# Chassis_Board.net
KiCad netlist of a schematic drawn in EAGLE
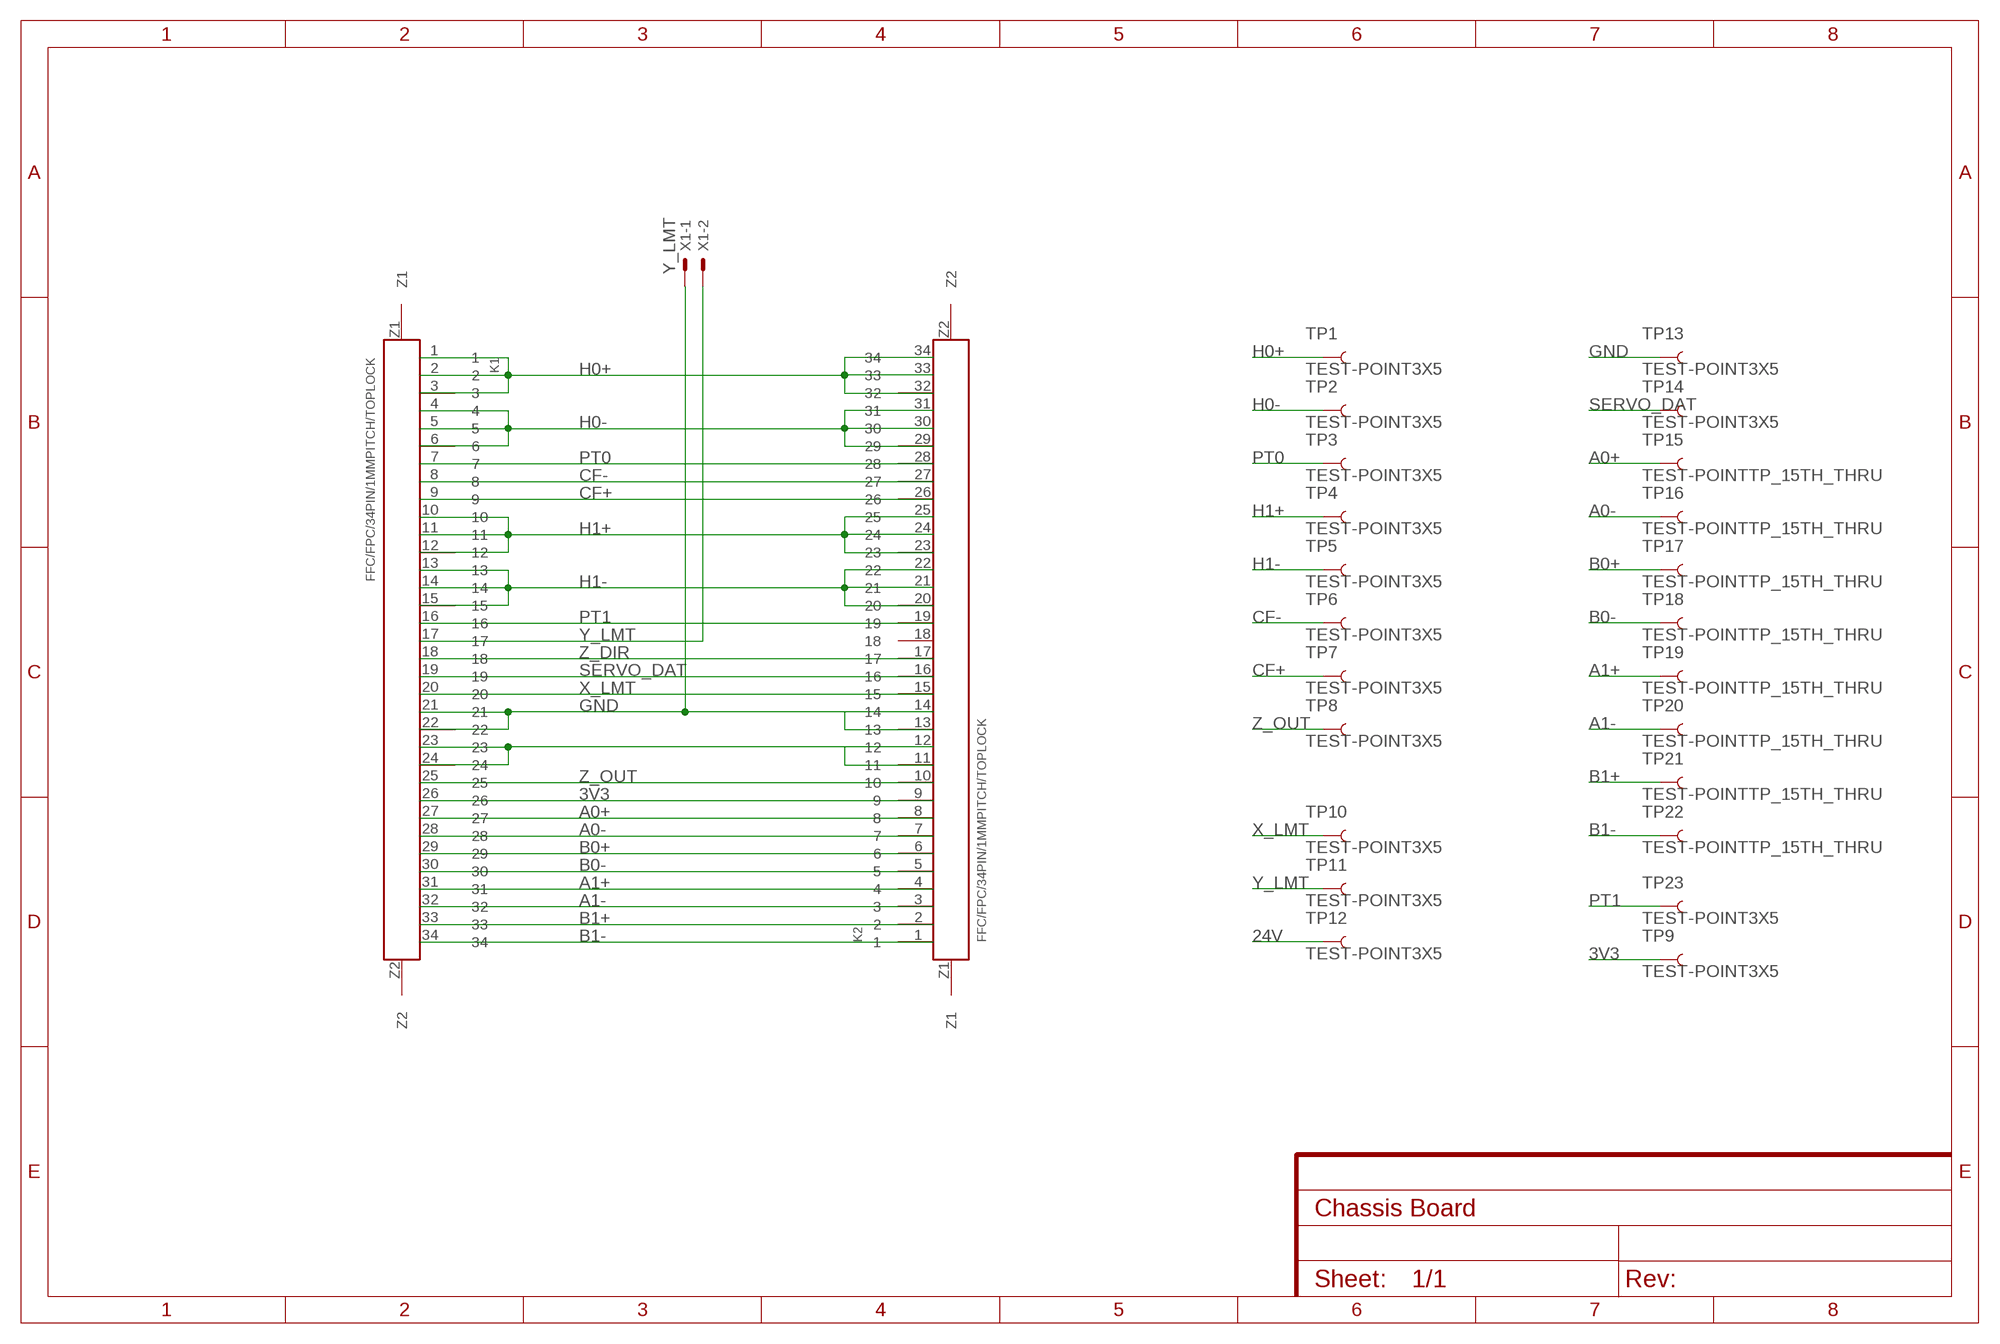
[diagram p0: schematic, sheet 1]

(export (version "E")
  (design (tool "Eeschema 10.0.6"))
  (components
    (comp (ref "K1")
      (value "FFC/FPC/34PIN/1MMPITCH/TOPLOCK")
      (footprint "eagle-import:34PIN_1MMPITCH_FFC_FPC")
      (libsource (lib "eagle-import") (part "FFC/FPC/34PIN/1MMPITCH/TOPLOCK"))
    )
    (comp (ref "K2")
      (value "FFC/FPC/34PIN/1MMPITCH/TOPLOCK")
      (footprint "eagle-import:34PIN_1MMPITCH_FFC_FPC")
      (libsource (lib "eagle-import") (part "FFC/FPC/34PIN/1MMPITCH/TOPLOCK"))
    )
    (comp (ref "TP1")
      (value "TEST-POINT3X5")
      (footprint "eagle-import:PAD.03X.05")
      (libsource (lib "eagle-import") (part "TEST-POINT3X5"))
    )
    (comp (ref "TP2")
      (value "TEST-POINT3X5")
      (footprint "eagle-import:PAD.03X.05")
      (libsource (lib "eagle-import") (part "TEST-POINT3X5"))
    )
    (comp (ref "TP3")
      (value "TEST-POINT3X5")
      (footprint "eagle-import:PAD.03X.05")
      (libsource (lib "eagle-import") (part "TEST-POINT3X5"))
    )
    (comp (ref "TP4")
      (value "TEST-POINT3X5")
      (footprint "eagle-import:PAD.03X.05")
      (libsource (lib "eagle-import") (part "TEST-POINT3X5"))
    )
    (comp (ref "TP5")
      (value "TEST-POINT3X5")
      (footprint "eagle-import:PAD.03X.05")
      (libsource (lib "eagle-import") (part "TEST-POINT3X5"))
    )
    (comp (ref "TP6")
      (value "TEST-POINT3X5")
      (footprint "eagle-import:PAD.03X.05")
      (libsource (lib "eagle-import") (part "TEST-POINT3X5"))
    )
    (comp (ref "TP7")
      (value "TEST-POINT3X5")
      (footprint "eagle-import:PAD.03X.05")
      (libsource (lib "eagle-import") (part "TEST-POINT3X5"))
    )
    (comp (ref "TP8")
      (value "TEST-POINT3X5")
      (footprint "eagle-import:PAD.03X.05")
      (libsource (lib "eagle-import") (part "TEST-POINT3X5"))
    )
    (comp (ref "TP9")
      (value "TEST-POINT3X5")
      (footprint "eagle-import:PAD.03X.05")
      (libsource (lib "eagle-import") (part "TEST-POINT3X5"))
    )
    (comp (ref "TP10")
      (value "TEST-POINT3X5")
      (footprint "eagle-import:PAD.03X.05")
      (libsource (lib "eagle-import") (part "TEST-POINT3X5"))
    )
    (comp (ref "TP11")
      (value "TEST-POINT3X5")
      (footprint "eagle-import:PAD.03X.05")
      (libsource (lib "eagle-import") (part "TEST-POINT3X5"))
    )
    (comp (ref "TP12")
      (value "TEST-POINT3X5")
      (footprint "eagle-import:PAD.03X.05")
      (libsource (lib "eagle-import") (part "TEST-POINT3X5"))
    )
    (comp (ref "TP13")
      (value "TEST-POINT3X5")
      (footprint "eagle-import:PAD.03X.05")
      (libsource (lib "eagle-import") (part "TEST-POINT3X5"))
    )
    (comp (ref "TP14")
      (value "TEST-POINT3X5")
      (footprint "eagle-import:PAD.03X.05")
      (libsource (lib "eagle-import") (part "TEST-POINT3X5"))
    )
    (comp (ref "TP15")
      (value "TEST-POINTTP_15TH_THRU")
      (footprint "eagle-import:TP_15TH")
      (libsource (lib "eagle-import") (part "TEST-POINTTP_15TH_THRU"))
    )
    (comp (ref "TP16")
      (value "TEST-POINTTP_15TH_THRU")
      (footprint "eagle-import:TP_15TH")
      (libsource (lib "eagle-import") (part "TEST-POINTTP_15TH_THRU"))
    )
    (comp (ref "TP17")
      (value "TEST-POINTTP_15TH_THRU")
      (footprint "eagle-import:TP_15TH")
      (libsource (lib "eagle-import") (part "TEST-POINTTP_15TH_THRU"))
    )
    (comp (ref "TP18")
      (value "TEST-POINTTP_15TH_THRU")
      (footprint "eagle-import:TP_15TH")
      (libsource (lib "eagle-import") (part "TEST-POINTTP_15TH_THRU"))
    )
    (comp (ref "TP19")
      (value "TEST-POINTTP_15TH_THRU")
      (footprint "eagle-import:TP_15TH")
      (libsource (lib "eagle-import") (part "TEST-POINTTP_15TH_THRU"))
    )
    (comp (ref "TP20")
      (value "TEST-POINTTP_15TH_THRU")
      (footprint "eagle-import:TP_15TH")
      (libsource (lib "eagle-import") (part "TEST-POINTTP_15TH_THRU"))
    )
    (comp (ref "TP21")
      (value "TEST-POINTTP_15TH_THRU")
      (footprint "eagle-import:TP_15TH")
      (libsource (lib "eagle-import") (part "TEST-POINTTP_15TH_THRU"))
    )
    (comp (ref "TP22")
      (value "TEST-POINTTP_15TH_THRU")
      (footprint "eagle-import:TP_15TH")
      (libsource (lib "eagle-import") (part "TEST-POINTTP_15TH_THRU"))
    )
    (comp (ref "TP23")
      (value "TEST-POINT3X5")
      (footprint "eagle-import:PAD.03X.05")
      (libsource (lib "eagle-import") (part "TEST-POINT3X5"))
    )
    (comp (ref "X1")
      (value "Y_LMT")
      (footprint "eagle-import:JST-XH-02-PACKAGE-LONG-PAD")
      (libsource (lib "eagle-import") (part "JST-XH-02-PIN-LONG-PAD"))
    )
  )
  (nets
    (net (code "1") (name "/3V3") (class "Default")
      (node (ref "K1") (pin "26") (pinfunction "26_26") (pintype "bidirectional"))
      (node (ref "K2") (pin "9") (pinfunction "9_9") (pintype "bidirectional"))
      (node (ref "TP9") (pin "P$1") (pinfunction "1_P$1") (pintype "bidirectional"))
    )
    (net (code "2") (name "/24V") (class "Default")
      (node (ref "K1") (pin "23") (pinfunction "23_23") (pintype "bidirectional"))
      (node (ref "K1") (pin "24") (pinfunction "24_24") (pintype "bidirectional"))
      (node (ref "K2") (pin "11") (pinfunction "11_11") (pintype "bidirectional"))
      (node (ref "K2") (pin "12") (pinfunction "12_12") (pintype "bidirectional"))
      (node (ref "TP12") (pin "P$1") (pinfunction "1_P$1") (pintype "bidirectional"))
    )
    (net (code "3") (name "/A0+") (class "Default")
      (node (ref "K1") (pin "27") (pinfunction "27_27") (pintype "bidirectional"))
      (node (ref "K2") (pin "8") (pinfunction "8_8") (pintype "bidirectional"))
      (node (ref "TP15") (pin "P$1") (pinfunction "1_P$1") (pintype "bidirectional"))
    )
    (net (code "4") (name "/A0-") (class "Default")
      (node (ref "K1") (pin "28") (pinfunction "28_28") (pintype "bidirectional"))
      (node (ref "K2") (pin "7") (pinfunction "7_7") (pintype "bidirectional"))
      (node (ref "TP16") (pin "P$1") (pinfunction "1_P$1") (pintype "bidirectional"))
    )
    (net (code "5") (name "/A1+") (class "Default")
      (node (ref "K1") (pin "31") (pinfunction "31_31") (pintype "bidirectional"))
      (node (ref "K2") (pin "4") (pinfunction "4_4") (pintype "bidirectional"))
      (node (ref "TP19") (pin "P$1") (pinfunction "1_P$1") (pintype "bidirectional"))
    )
    (net (code "6") (name "/A1-") (class "Default")
      (node (ref "K1") (pin "32") (pinfunction "32_32") (pintype "bidirectional"))
      (node (ref "K2") (pin "3") (pinfunction "3_3") (pintype "bidirectional"))
      (node (ref "TP20") (pin "P$1") (pinfunction "1_P$1") (pintype "bidirectional"))
    )
    (net (code "7") (name "/B0+") (class "Default")
      (node (ref "K1") (pin "29") (pinfunction "29_29") (pintype "bidirectional"))
      (node (ref "K2") (pin "6") (pinfunction "6_6") (pintype "bidirectional"))
      (node (ref "TP17") (pin "P$1") (pinfunction "1_P$1") (pintype "bidirectional"))
    )
    (net (code "8") (name "/B0-") (class "Default")
      (node (ref "K1") (pin "30") (pinfunction "30_30") (pintype "bidirectional"))
      (node (ref "K2") (pin "5") (pinfunction "5_5") (pintype "bidirectional"))
      (node (ref "TP18") (pin "P$1") (pinfunction "1_P$1") (pintype "bidirectional"))
    )
    (net (code "9") (name "/B1+") (class "Default")
      (node (ref "K1") (pin "33") (pinfunction "33_33") (pintype "bidirectional"))
      (node (ref "K2") (pin "2") (pinfunction "2_2") (pintype "bidirectional"))
      (node (ref "TP21") (pin "P$1") (pinfunction "1_P$1") (pintype "bidirectional"))
    )
    (net (code "10") (name "/B1-") (class "Default")
      (node (ref "K1") (pin "34") (pinfunction "34_34") (pintype "bidirectional"))
      (node (ref "K2") (pin "1") (pinfunction "1_1") (pintype "bidirectional"))
      (node (ref "TP22") (pin "P$1") (pinfunction "1_P$1") (pintype "bidirectional"))
    )
    (net (code "11") (name "/CF+") (class "Default")
      (node (ref "K1") (pin "9") (pinfunction "9_9") (pintype "bidirectional"))
      (node (ref "K2") (pin "26") (pinfunction "26_26") (pintype "bidirectional"))
      (node (ref "TP7") (pin "P$1") (pinfunction "1_P$1") (pintype "bidirectional"))
    )
    (net (code "12") (name "/CF-") (class "Default")
      (node (ref "K1") (pin "8") (pinfunction "8_8") (pintype "bidirectional"))
      (node (ref "K2") (pin "27") (pinfunction "27_27") (pintype "bidirectional"))
      (node (ref "TP6") (pin "P$1") (pinfunction "1_P$1") (pintype "bidirectional"))
    )
    (net (code "13") (name "/GND") (class "Default")
      (node (ref "K1") (pin "21") (pinfunction "21_21") (pintype "bidirectional"))
      (node (ref "K1") (pin "22") (pinfunction "22_22") (pintype "bidirectional"))
      (node (ref "K2") (pin "13") (pinfunction "13_13") (pintype "bidirectional"))
      (node (ref "K2") (pin "14") (pinfunction "14_14") (pintype "bidirectional"))
      (node (ref "TP13") (pin "P$1") (pinfunction "1_P$1") (pintype "bidirectional"))
      (node (ref "X1") (pin "1") (pinfunction "S_1") (pintype "passive"))
    )
    (net (code "14") (name "/H0+") (class "Default")
      (node (ref "K1") (pin "1") (pinfunction "1_1") (pintype "bidirectional"))
      (node (ref "K1") (pin "2") (pinfunction "2_2") (pintype "bidirectional"))
      (node (ref "K1") (pin "3") (pinfunction "3_3") (pintype "bidirectional"))
      (node (ref "K2") (pin "32") (pinfunction "32_32") (pintype "bidirectional"))
      (node (ref "K2") (pin "33") (pinfunction "33_33") (pintype "bidirectional"))
      (node (ref "K2") (pin "34") (pinfunction "34_34") (pintype "bidirectional"))
      (node (ref "TP1") (pin "P$1") (pinfunction "1_P$1") (pintype "bidirectional"))
    )
    (net (code "15") (name "/H0-") (class "Default")
      (node (ref "K1") (pin "4") (pinfunction "4_4") (pintype "bidirectional"))
      (node (ref "K1") (pin "5") (pinfunction "5_5") (pintype "bidirectional"))
      (node (ref "K1") (pin "6") (pinfunction "6_6") (pintype "bidirectional"))
      (node (ref "K2") (pin "29") (pinfunction "29_29") (pintype "bidirectional"))
      (node (ref "K2") (pin "30") (pinfunction "30_30") (pintype "bidirectional"))
      (node (ref "K2") (pin "31") (pinfunction "31_31") (pintype "bidirectional"))
      (node (ref "TP2") (pin "P$1") (pinfunction "1_P$1") (pintype "bidirectional"))
    )
    (net (code "16") (name "/H1+") (class "Default")
      (node (ref "K1") (pin "10") (pinfunction "10_10") (pintype "bidirectional"))
      (node (ref "K1") (pin "11") (pinfunction "11_11") (pintype "bidirectional"))
      (node (ref "K1") (pin "12") (pinfunction "12_12") (pintype "bidirectional"))
      (node (ref "K2") (pin "23") (pinfunction "23_23") (pintype "bidirectional"))
      (node (ref "K2") (pin "24") (pinfunction "24_24") (pintype "bidirectional"))
      (node (ref "K2") (pin "25") (pinfunction "25_25") (pintype "bidirectional"))
      (node (ref "TP4") (pin "P$1") (pinfunction "1_P$1") (pintype "bidirectional"))
    )
    (net (code "17") (name "/H1-") (class "Default")
      (node (ref "K1") (pin "13") (pinfunction "13_13") (pintype "bidirectional"))
      (node (ref "K1") (pin "14") (pinfunction "14_14") (pintype "bidirectional"))
      (node (ref "K1") (pin "15") (pinfunction "15_15") (pintype "bidirectional"))
      (node (ref "K2") (pin "20") (pinfunction "20_20") (pintype "bidirectional"))
      (node (ref "K2") (pin "21") (pinfunction "21_21") (pintype "bidirectional"))
      (node (ref "K2") (pin "22") (pinfunction "22_22") (pintype "bidirectional"))
      (node (ref "TP5") (pin "P$1") (pinfunction "1_P$1") (pintype "bidirectional"))
    )
    (net (code "18") (name "/PT0") (class "Default")
      (node (ref "K1") (pin "7") (pinfunction "7_7") (pintype "bidirectional"))
      (node (ref "K2") (pin "28") (pinfunction "28_28") (pintype "bidirectional"))
      (node (ref "TP3") (pin "P$1") (pinfunction "1_P$1") (pintype "bidirectional"))
    )
    (net (code "19") (name "/PT1") (class "Default")
      (node (ref "K1") (pin "16") (pinfunction "16_16") (pintype "bidirectional"))
      (node (ref "K2") (pin "19") (pinfunction "19_19") (pintype "bidirectional"))
      (node (ref "TP23") (pin "P$1") (pinfunction "1_P$1") (pintype "bidirectional"))
    )
    (net (code "20") (name "/SERVO_DAT") (class "Default")
      (node (ref "K1") (pin "19") (pinfunction "19_19") (pintype "bidirectional"))
      (node (ref "K2") (pin "16") (pinfunction "16_16") (pintype "bidirectional"))
      (node (ref "TP14") (pin "P$1") (pinfunction "1_P$1") (pintype "bidirectional"))
    )
    (net (code "21") (name "/X_LMT") (class "Default")
      (node (ref "K1") (pin "20") (pinfunction "20_20") (pintype "bidirectional"))
      (node (ref "K2") (pin "15") (pinfunction "15_15") (pintype "bidirectional"))
      (node (ref "TP10") (pin "P$1") (pinfunction "1_P$1") (pintype "bidirectional"))
    )
    (net (code "22") (name "/Y_LMT") (class "Default")
      (node (ref "K1") (pin "17") (pinfunction "17_17") (pintype "bidirectional"))
      (node (ref "TP11") (pin "P$1") (pinfunction "1_P$1") (pintype "bidirectional"))
      (node (ref "X1") (pin "2") (pinfunction "S_2") (pintype "passive"))
    )
    (net (code "23") (name "/Z_DIR") (class "Default")
      (node (ref "K1") (pin "18") (pinfunction "18_18") (pintype "bidirectional"))
      (node (ref "K2") (pin "17") (pinfunction "17_17") (pintype "bidirectional"))
    )
    (net (code "24") (name "/Z_OUT") (class "Default")
      (node (ref "K1") (pin "25") (pinfunction "25_25") (pintype "bidirectional"))
      (node (ref "K2") (pin "10") (pinfunction "10_10") (pintype "bidirectional"))
      (node (ref "TP8") (pin "P$1") (pinfunction "1_P$1") (pintype "bidirectional"))
    )
    (net (code "25") (name "unconnected-(K1-PadZ1)") (class "Default")
      (node (ref "K1") (pin "Z1") (pinfunction "Z1_Z1") (pintype "bidirectional"))
    )
    (net (code "26") (name "unconnected-(K1-PadZ2)") (class "Default")
      (node (ref "K1") (pin "Z2") (pinfunction "Z2_Z2") (pintype "bidirectional"))
    )
    (net (code "27") (name "unconnected-(K2-Pad18)") (class "Default")
      (node (ref "K2") (pin "18") (pinfunction "18_18") (pintype "bidirectional"))
    )
    (net (code "28") (name "unconnected-(K2-PadZ1)") (class "Default")
      (node (ref "K2") (pin "Z1") (pinfunction "Z1_Z1") (pintype "bidirectional"))
    )
    (net (code "29") (name "unconnected-(K2-PadZ2)") (class "Default")
      (node (ref "K2") (pin "Z2") (pinfunction "Z2_Z2") (pintype "bidirectional"))
    )
  )
)
